# 3_Alimentacion.net
KiCad netlist of a schematic drawn in Altium Designer
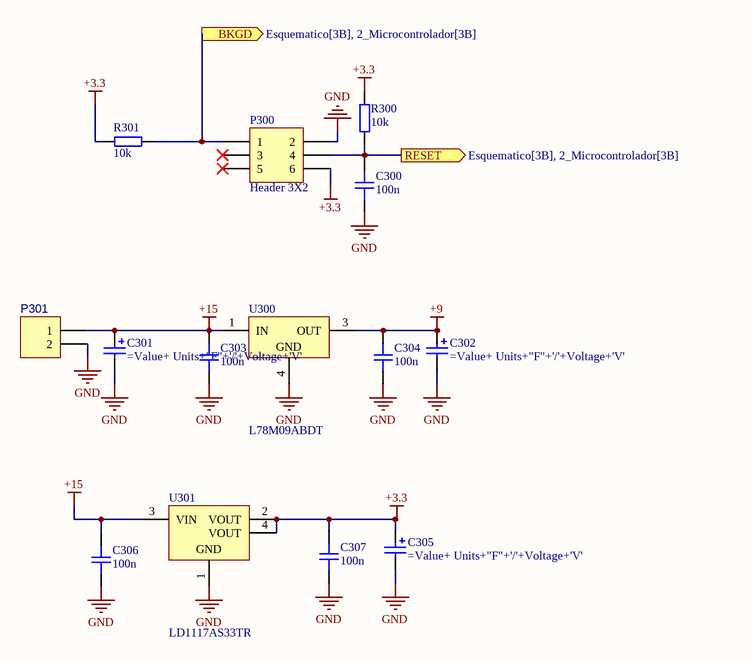
[diagram p0: 3_Alimentacion.SchDoc]

(export (version "E")
  (design (tool "Eeschema 10.0.6"))
  (components
    (comp (ref "C300")
      (value "100n")
      (footprint "CAP_0603")
      (description "Capacitor SMD 0603")
      (libsource (lib "Schematic-Lib-PhilsLab") (part "CAP_0603"))
    )
    (comp (ref "C301")
      (value "47u/16V")
      (footprint "C SIZE SMD CAPACITOR")
      (description "Capacitor Electr. Alum. SMD WxLxH 6.3x6.3x5.3 Ǿ= 6 mm")
      (fields
        (field (name "MANUFACTURER") "Generic Components")
        (field (name "VOLTAGE") "16")
        (field (name "PUBLISHER") "Altium Hobart Technology Centre")
      )
      (libsource (lib "COMB GEN 1") (part "Cap Pol1"))
    )
    (comp (ref "C302")
      (value "47u/16V")
      (footprint "C SIZE SMD CAPACITOR")
      (description "Capacitor Electr. Alum. SMD WxLxH 6.3x6.3x5.3 Ǿ= 6 mm")
      (fields
        (field (name "MANUFACTURER") "Generic Components")
        (field (name "VOLTAGE") "16")
        (field (name "PUBLISHER") "Altium Hobart Technology Centre")
      )
      (libsource (lib "COMB GEN 1") (part "Cap Pol1"))
    )
    (comp (ref "C303")
      (value "100n")
      (footprint "CAP_0603")
      (description "Capacitor SMD 0603")
      (libsource (lib "Schematic-Lib-PhilsLab") (part "CAP_0603"))
    )
    (comp (ref "C304")
      (value "100n")
      (footprint "CAP_0603")
      (description "Capacitor SMD 0603")
      (libsource (lib "Schematic-Lib-PhilsLab") (part "CAP_0603"))
    )
    (comp (ref "C305")
      (value "47u/16V")
      (footprint "C SIZE SMD CAPACITOR")
      (description "Capacitor Electr. Alum. SMD WxLxH 6.3x6.3x5.3 Ǿ= 6 mm")
      (fields
        (field (name "MANUFACTURER") "Generic Components")
        (field (name "VOLTAGE") "16")
        (field (name "PUBLISHER") "Altium Hobart Technology Centre")
      )
      (libsource (lib "COMB GEN 1") (part "Cap Pol1"))
    )
    (comp (ref "C306")
      (value "100n")
      (footprint "CAP_0603")
      (description "Capacitor SMD 0603")
      (libsource (lib "Schematic-Lib-PhilsLab") (part "CAP_0603"))
    )
    (comp (ref "C307")
      (value "100n")
      (footprint "CAP_0603")
      (description "Capacitor SMD 0603")
      (libsource (lib "Schematic-Lib-PhilsLab") (part "CAP_0603"))
    )
    (comp (ref "P300")
      (value "Header 3X2")
      (footprint "HDR2X3")
      (description "Header, 3-Pin, Dual row")
      (fields (field (name "PUBLISHER") "Altium Limited"))
      (libsource (lib "Miscellaneous Connectors") (part "Header 3X2"))
    )
    (comp (ref "P301")
      (value "Conector Molex 2 vias Macho")
      (footprint "MOLEX INDENT 2 LOW PRF")
      (description "Header, 2-Pin")
      (fields (field (name "PUBLISHER") "Altium Limited"))
      (libsource (lib "COMB GEN 1") (part "Header 2"))
    )
    (comp (ref "R300")
      (value "10k")
      (footprint "RES_0603")
      (description "Resistor SMD 0603")
      (libsource (lib "Schematic-Lib-PhilsLab") (part "RES_0603"))
    )
    (comp (ref "R301")
      (value "10k")
      (footprint "RES_0603")
      (description "Resistor SMD 0603")
      (libsource (lib "Schematic-Lib-PhilsLab") (part "RES_0603"))
    )
    (comp (ref "U300")
      (value "L78M09ABDT")
      (footprint "TO-252")
      (description "Precision 500mA Regulator")
      (fields (field (name "PUBLISHER") "Altium Limited"))
      (libsource (lib "ST Power Mgt Voltage Regulator") (part "L78M09ABDT"))
    )
    (comp (ref "U301")
      (value "LD1117AS33TR")
      (footprint "SOT-223_N")
      (description "1A, Low Drop Positive Voltage Regulator, 3.3V, 4-Pin SOT-223, Tape and Reel")
      (libsource (lib "STMicroelectronics Power Management Linear Regulator") (part "LD1117AS33TR"))
    )
  )
  (nets
    (net (code "1") (name "+3.3") (class "Default")
      (node (ref "C305") (pin "1") (pinfunction "1_1") (pintype "passive"))
      (node (ref "C307") (pin "1") (pinfunction "1_1") (pintype "passive"))
      (node (ref "P300") (pin "6") (pinfunction "6_6") (pintype "passive"))
      (node (ref "R300") (pin "1") (pinfunction "1_1") (pintype "passive"))
      (node (ref "R301") (pin "2") (pinfunction "2_2") (pintype "passive"))
      (node (ref "U301") (pin "2") (pinfunction "VOUT_2") (pintype "power_in"))
      (node (ref "U301") (pin "4") (pinfunction "VOUT_4") (pintype "power_in"))
    )
    (net (code "2") (name "+9") (class "Default")
      (node (ref "C302") (pin "1") (pinfunction "1_1") (pintype "passive"))
      (node (ref "C304") (pin "1") (pinfunction "1_1") (pintype "passive"))
      (node (ref "U300") (pin "3") (pinfunction "OUT_3") (pintype "power_in"))
    )
    (net (code "3") (name "+15") (class "Default")
      (node (ref "C301") (pin "1") (pinfunction "1_1") (pintype "passive"))
      (node (ref "C303") (pin "1") (pinfunction "1_1") (pintype "passive"))
      (node (ref "C306") (pin "1") (pinfunction "1_1") (pintype "passive"))
      (node (ref "P301") (pin "1") (pinfunction "1_1") (pintype "passive"))
      (node (ref "U300") (pin "1") (pinfunction "IN_1") (pintype "power_in"))
      (node (ref "U301") (pin "3") (pinfunction "VIN_3") (pintype "power_in"))
    )
    (net (code "4") (name "/BKGD") (class "Default")
      (node (ref "P300") (pin "1") (pinfunction "1_1") (pintype "passive"))
      (node (ref "R301") (pin "1") (pinfunction "1_1") (pintype "passive"))
    )
    (net (code "5") (name "/RESET") (class "Default")
      (node (ref "C300") (pin "1") (pinfunction "1_1") (pintype "passive"))
      (node (ref "P300") (pin "4") (pinfunction "4_4") (pintype "passive"))
      (node (ref "R300") (pin "2") (pinfunction "2_2") (pintype "passive"))
    )
    (net (code "6") (name "GND") (class "Default")
      (node (ref "C300") (pin "2") (pinfunction "2_2") (pintype "passive"))
      (node (ref "C301") (pin "2") (pinfunction "2_2") (pintype "passive"))
      (node (ref "C302") (pin "2") (pinfunction "2_2") (pintype "passive"))
      (node (ref "C303") (pin "2") (pinfunction "2_2") (pintype "passive"))
      (node (ref "C304") (pin "2") (pinfunction "2_2") (pintype "passive"))
      (node (ref "C305") (pin "2") (pinfunction "2_2") (pintype "passive"))
      (node (ref "C306") (pin "2") (pinfunction "2_2") (pintype "passive"))
      (node (ref "C307") (pin "2") (pinfunction "2_2") (pintype "passive"))
      (node (ref "P300") (pin "2") (pinfunction "2_2") (pintype "passive"))
      (node (ref "P301") (pin "2") (pinfunction "2_2") (pintype "passive"))
      (node (ref "U300") (pin "4") (pinfunction "GND_4") (pintype "power_in"))
      (node (ref "U301") (pin "1") (pinfunction "GND_1") (pintype "power_in"))
    )
    (net (code "7") (name "unconnected-(P300-Pad3)") (class "Default")
      (node (ref "P300") (pin "3") (pinfunction "3_3") (pintype "passive+no_connect"))
    )
    (net (code "8") (name "unconnected-(P300-Pad5)") (class "Default")
      (node (ref "P300") (pin "5") (pinfunction "5_5") (pintype "passive+no_connect"))
    )
  )
)
